# sokolov_control_board_3.net
KiCad netlist of a schematic drawn in Altium Designer
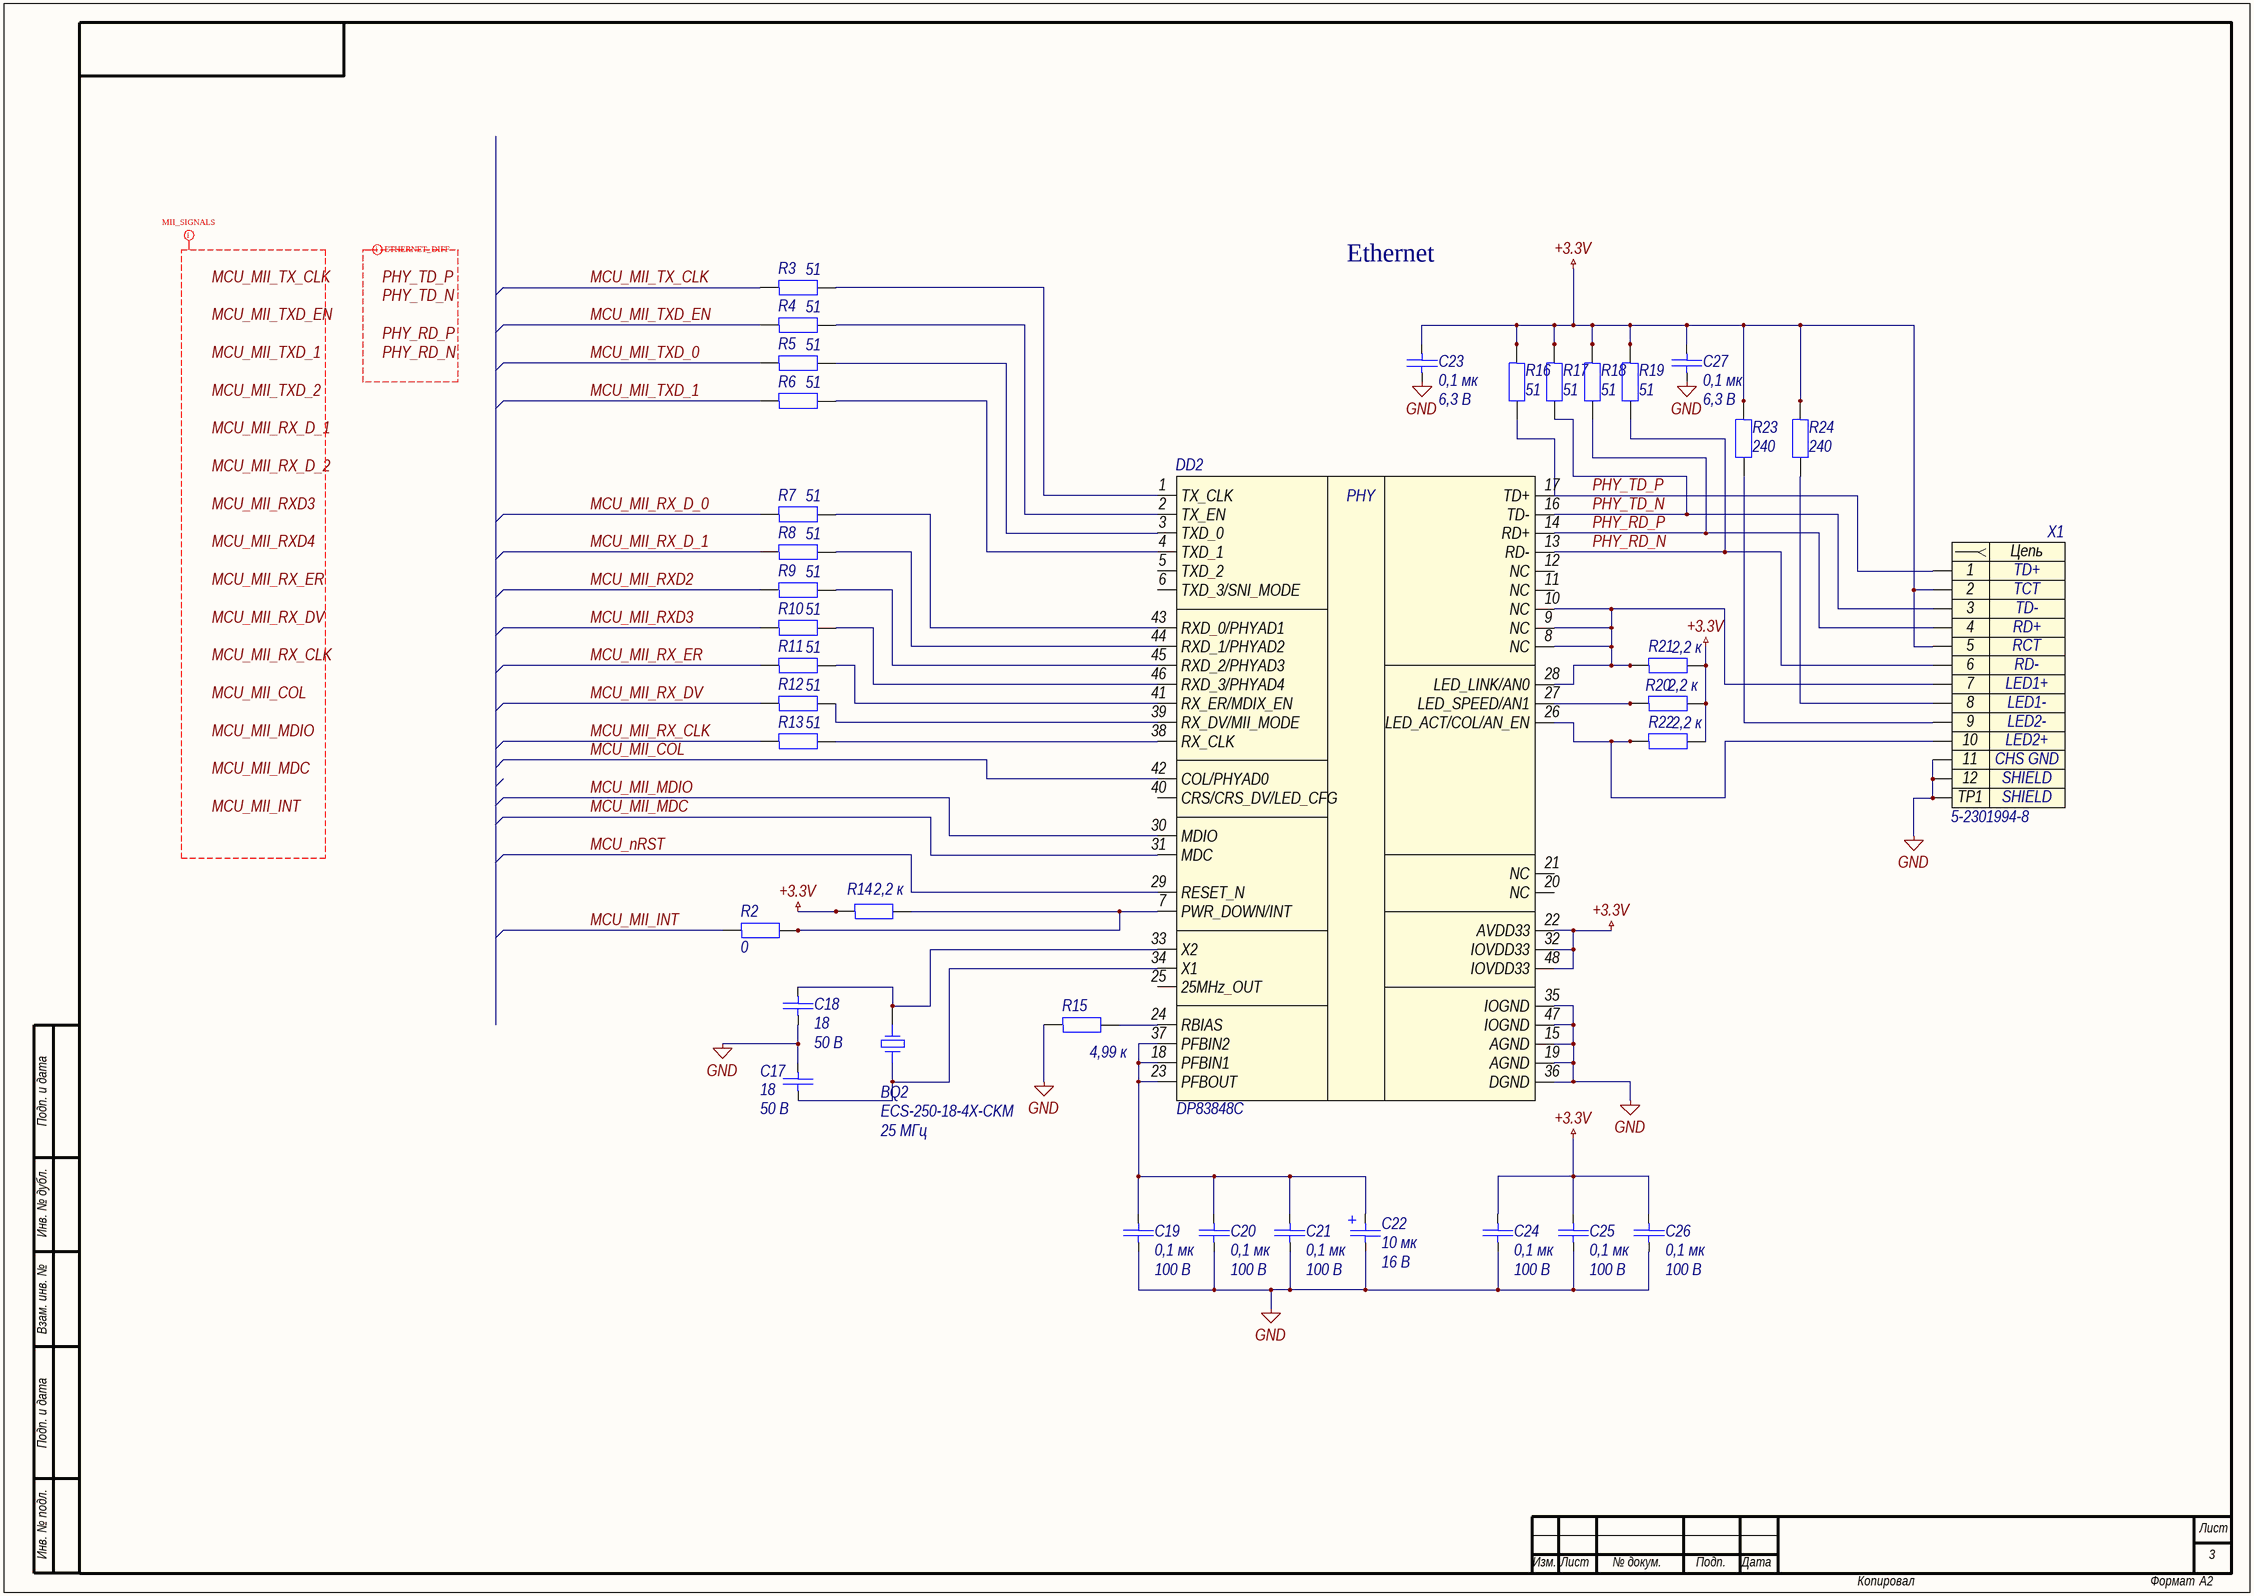
[diagram p0: sokolov_control_board_3.SchDoc]

(export (version "E")
  (design (tool "Eeschema 10.0.6"))
  (components
    (comp (ref "BQ2")
      (value "ECS-250-18-4X-CKM")
      (footprint "HC-49/US")
      (description "=Описание")
      (fields (field (name "ЧАСТОТA") "25 МГц"))
      (libsource (lib "Database_Students") (part "RESONATOR-COMMON"))
    )
    (comp (ref "C17")
      (value "18")
      (footprint "C0603")
      (description "=Описание")
      (fields (field (name "НАПРЯЖЕНИЕ") "50 В"))
      (libsource (lib "Database_Students") (part "CAPACITOR-NONPOLAR"))
    )
    (comp (ref "C18")
      (value "18")
      (footprint "C0603")
      (description "=Описание")
      (fields (field (name "НАПРЯЖЕНИЕ") "50 В"))
      (libsource (lib "Database_Students") (part "CAPACITOR-NONPOLAR"))
    )
    (comp (ref "C19")
      (value "0,1 мк")
      (footprint "C0603")
      (description "=Описание")
      (fields (field (name "НАПРЯЖЕНИЕ") "100 В"))
      (libsource (lib "Database_Students") (part "CAPACITOR-NONPOLAR"))
    )
    (comp (ref "C20")
      (value "0,1 мк")
      (footprint "C0603")
      (description "=Описание")
      (fields (field (name "НАПРЯЖЕНИЕ") "100 В"))
      (libsource (lib "Database_Students") (part "CAPACITOR-NONPOLAR"))
    )
    (comp (ref "C21")
      (value "0,1 мк")
      (footprint "C0603")
      (description "=Описание")
      (fields (field (name "НАПРЯЖЕНИЕ") "100 В"))
      (libsource (lib "Database_Students") (part "CAPACITOR-NONPOLAR"))
    )
    (comp (ref "C22")
      (value "10 мк")
      (footprint "C3216-18")
      (description "=Описание")
      (fields (field (name "НАПРЯЖЕНИЕ") "16 В"))
      (libsource (lib "Database_Students") (part "CAPACITOR-POLAR"))
    )
    (comp (ref "C23")
      (value "0,1 мк")
      (footprint "C0402")
      (description "=Описание")
      (fields (field (name "НАПРЯЖЕНИЕ") "6,3 В"))
      (libsource (lib "Database_Students") (part "CAPACITOR-NONPOLAR"))
    )
    (comp (ref "C24")
      (value "0,1 мк")
      (footprint "C0603")
      (description "=Описание")
      (fields (field (name "НАПРЯЖЕНИЕ") "100 В"))
      (libsource (lib "Database_Students") (part "CAPACITOR-NONPOLAR"))
    )
    (comp (ref "C25")
      (value "0,1 мк")
      (footprint "C0603")
      (description "=Описание")
      (fields (field (name "НАПРЯЖЕНИЕ") "100 В"))
      (libsource (lib "Database_Students") (part "CAPACITOR-NONPOLAR"))
    )
    (comp (ref "C26")
      (value "0,1 мк")
      (footprint "C0603")
      (description "=Описание")
      (fields (field (name "НАПРЯЖЕНИЕ") "100 В"))
      (libsource (lib "Database_Students") (part "CAPACITOR-NONPOLAR"))
    )
    (comp (ref "C27")
      (value "0,1 мк")
      (footprint "C0402")
      (description "=Описание")
      (fields (field (name "НАПРЯЖЕНИЕ") "6,3 В"))
      (libsource (lib "Database_Students") (part "CAPACITOR-NONPOLAR"))
    )
    (comp (ref "DD2")
      (value "DP83848C")
      (footprint "LQFP-48-P50-700X700X160-L60X22")
      (description "=Описание")
      (fields
        (field (name "PARTNUMBER") "DP83848CVV")
        (field (name "MANUFACTURER") "NationalSemiconductor")
        (field (name "COPYRIGHT") "Copyright (C) 2018 Accelerated Designs. All rights reserved")
        (field (name "PUBLISHER") "AltiumLimited")
      )
      (libsource (lib "Database_Students") (part "DP83848CVV"))
    )
    (comp (ref "R2")
      (value "0")
      (footprint "R0603")
      (description "=Описание")
      (libsource (lib "Database_Students") (part "RESISTOR-COMMON"))
    )
    (comp (ref "R3")
      (value "51")
      (footprint "R0603")
      (description "=Описание")
      (libsource (lib "Database_Students") (part "RESISTOR-COMMON"))
    )
    (comp (ref "R4")
      (value "51")
      (footprint "R0603")
      (description "=Описание")
      (libsource (lib "Database_Students") (part "RESISTOR-COMMON"))
    )
    (comp (ref "R5")
      (value "51")
      (footprint "R0603")
      (description "=Описание")
      (libsource (lib "Database_Students") (part "RESISTOR-COMMON"))
    )
    (comp (ref "R6")
      (value "51")
      (footprint "R0603")
      (description "=Описание")
      (libsource (lib "Database_Students") (part "RESISTOR-COMMON"))
    )
    (comp (ref "R7")
      (value "51")
      (footprint "R0603")
      (description "=Описание")
      (libsource (lib "Database_Students") (part "RESISTOR-COMMON"))
    )
    (comp (ref "R8")
      (value "51")
      (footprint "R0603")
      (description "=Описание")
      (libsource (lib "Database_Students") (part "RESISTOR-COMMON"))
    )
    (comp (ref "R9")
      (value "51")
      (footprint "R0603")
      (description "=Описание")
      (libsource (lib "Database_Students") (part "RESISTOR-COMMON"))
    )
    (comp (ref "R10")
      (value "51")
      (footprint "R0603")
      (description "=Описание")
      (libsource (lib "Database_Students") (part "RESISTOR-COMMON"))
    )
    (comp (ref "R11")
      (value "51")
      (footprint "R0603")
      (description "=Описание")
      (libsource (lib "Database_Students") (part "RESISTOR-COMMON"))
    )
    (comp (ref "R12")
      (value "51")
      (footprint "R0603")
      (description "=Описание")
      (libsource (lib "Database_Students") (part "RESISTOR-COMMON"))
    )
    (comp (ref "R13")
      (value "51")
      (footprint "R0603")
      (description "=Описание")
      (libsource (lib "Database_Students") (part "RESISTOR-COMMON"))
    )
    (comp (ref "R14")
      (value "2,2 к")
      (footprint "R0603")
      (description "=Описание")
      (libsource (lib "Database_Students") (part "RESISTOR-COMMON"))
    )
    (comp (ref "R15")
      (value "4,99 к")
      (footprint "R0603")
      (description "=Описание")
      (libsource (lib "Database_Students") (part "RESISTOR-COMMON"))
    )
    (comp (ref "R16")
      (value "51")
      (footprint "R0603")
      (description "=Описание")
      (libsource (lib "Database_Students") (part "RESISTOR-COMMON"))
    )
    (comp (ref "R17")
      (value "51")
      (footprint "R0603")
      (description "=Описание")
      (libsource (lib "Database_Students") (part "RESISTOR-COMMON"))
    )
    (comp (ref "R18")
      (value "51")
      (footprint "R0603")
      (description "=Описание")
      (libsource (lib "Database_Students") (part "RESISTOR-COMMON"))
    )
    (comp (ref "R19")
      (value "51")
      (footprint "R0603")
      (description "=Описание")
      (libsource (lib "Database_Students") (part "RESISTOR-COMMON"))
    )
    (comp (ref "R20")
      (value "2,2 к")
      (footprint "R0603")
      (description "=Описание")
      (libsource (lib "Database_Students") (part "RESISTOR-COMMON"))
    )
    (comp (ref "R21")
      (value "2,2 к")
      (footprint "R0603")
      (description "=Описание")
      (libsource (lib "Database_Students") (part "RESISTOR-COMMON"))
    )
    (comp (ref "R22")
      (value "2,2 к")
      (footprint "R0603")
      (description "=Описание")
      (libsource (lib "Database_Students") (part "RESISTOR-COMMON"))
    )
    (comp (ref "R23")
      (value "240")
      (footprint "R0603")
      (description "=Описание")
      (libsource (lib "Database_Students") (part "RESISTOR-COMMON"))
    )
    (comp (ref "R24")
      (value "240")
      (footprint "R0603")
      (description "=Описание")
      (libsource (lib "Database_Students") (part "RESISTOR-COMMON"))
    )
    (comp (ref "X1")
      (value "5-2301994-8")
      (footprint "5-2301994-8")
      (description "=Описание")
      (libsource (lib "Database_Students") (part "HEADER-12-TP1-SCT"))
    )
  )
  (nets
    (net (code "1") (name "+3.3V") (class "Default")
      (node (ref "C23") (pin "2") (pinfunction "2_2") (pintype "passive"))
      (node (ref "C24") (pin "2") (pinfunction "2_2") (pintype "passive"))
      (node (ref "C25") (pin "2") (pinfunction "2_2") (pintype "passive"))
      (node (ref "C26") (pin "2") (pinfunction "2_2") (pintype "passive"))
      (node (ref "C27") (pin "2") (pinfunction "2_2") (pintype "passive"))
      (node (ref "DD2") (pin "22") (pinfunction "AVDD33_22") (pintype "power_in"))
      (node (ref "DD2") (pin "32") (pinfunction "IOVDD33_32") (pintype "power_in"))
      (node (ref "DD2") (pin "48") (pinfunction "IOVDD33_48") (pintype "power_in"))
      (node (ref "R14") (pin "1") (pinfunction "1_1") (pintype "passive"))
      (node (ref "R16") (pin "1") (pinfunction "1_1") (pintype "passive"))
      (node (ref "R17") (pin "1") (pinfunction "1_1") (pintype "passive"))
      (node (ref "R18") (pin "1") (pinfunction "1_1") (pintype "passive"))
      (node (ref "R19") (pin "1") (pinfunction "1_1") (pintype "passive"))
      (node (ref "R20") (pin "2") (pinfunction "2_2") (pintype "passive"))
      (node (ref "R21") (pin "2") (pinfunction "2_2") (pintype "passive"))
      (node (ref "R22") (pin "2") (pinfunction "2_2") (pintype "passive"))
      (node (ref "R23") (pin "1") (pinfunction "1_1") (pintype "passive"))
      (node (ref "R24") (pin "1") (pinfunction "1_1") (pintype "passive"))
      (node (ref "X1") (pin "2") (pinfunction "2_2") (pintype "passive"))
      (node (ref "X1") (pin "5") (pinfunction "5_5") (pintype "passive"))
    )
    (net (code "2") (name "/MCU_MII_COL") (class "Default")
      (node (ref "DD2") (pin "42") (pinfunction "COL/PHYAD0_42") (pintype "power_in"))
    )
    (net (code "3") (name "/MCU_MII_INT") (class "Default")
      (node (ref "R2") (pin "1") (pinfunction "1_1") (pintype "passive"))
    )
    (net (code "4") (name "/MCU_MII_MDC") (class "Default")
      (node (ref "DD2") (pin "31") (pinfunction "MDC_31") (pintype "power_in"))
    )
    (net (code "5") (name "/MCU_MII_MDIO") (class "Default")
      (node (ref "DD2") (pin "30") (pinfunction "MDIO_30") (pintype "power_in"))
    )
    (net (code "6") (name "/MCU_MII_RXD2") (class "Default")
      (node (ref "R9") (pin "1") (pinfunction "1_1") (pintype "passive"))
    )
    (net (code "7") (name "/MCU_MII_RXD3") (class "Default")
      (node (ref "R10") (pin "1") (pinfunction "1_1") (pintype "passive"))
    )
    (net (code "9") (name "/MCU_MII_RX_CLK") (class "Default")
      (node (ref "R13") (pin "1") (pinfunction "1_1") (pintype "passive"))
    )
    (net (code "10") (name "/MCU_MII_RX_DV") (class "Default")
      (node (ref "R12") (pin "1") (pinfunction "1_1") (pintype "passive"))
    )
    (net (code "11") (name "/MCU_MII_RX_D_0") (class "Default")
      (node (ref "R7") (pin "1") (pinfunction "1_1") (pintype "passive"))
    )
    (net (code "12") (name "/MCU_MII_RX_D_1") (class "Default")
      (node (ref "R8") (pin "1") (pinfunction "1_1") (pintype "passive"))
    )
    (net (code "14") (name "/MCU_MII_RX_ER") (class "Default")
      (node (ref "R11") (pin "1") (pinfunction "1_1") (pintype "passive"))
    )
    (net (code "15") (name "/MCU_MII_TXD_0") (class "Default")
      (node (ref "R5") (pin "1") (pinfunction "1_1") (pintype "passive"))
    )
    (net (code "16") (name "/MCU_MII_TXD_1") (class "Default")
      (node (ref "R6") (pin "1") (pinfunction "1_1") (pintype "passive"))
    )
    (net (code "18") (name "/MCU_MII_TXD_EN") (class "Default")
      (node (ref "R4") (pin "1") (pinfunction "1_1") (pintype "passive"))
    )
    (net (code "19") (name "/MCU_MII_TX_CLK") (class "Default")
      (node (ref "R3") (pin "1") (pinfunction "1_1") (pintype "passive"))
    )
    (net (code "20") (name "/MCU_nRST") (class "Default")
      (node (ref "DD2") (pin "29") (pinfunction "RESET_N_29") (pintype "power_in"))
    )
    (net (code "21") (name "/PHY_RD_N") (class "Default")
      (node (ref "DD2") (pin "13") (pinfunction "RD-_13") (pintype "power_in"))
      (node (ref "R19") (pin "2") (pinfunction "2_2") (pintype "passive"))
      (node (ref "X1") (pin "6") (pinfunction "6_6") (pintype "passive"))
    )
    (net (code "22") (name "/PHY_RD_P") (class "Default")
      (node (ref "DD2") (pin "14") (pinfunction "RD+_14") (pintype "power_in"))
      (node (ref "R18") (pin "2") (pinfunction "2_2") (pintype "passive"))
      (node (ref "X1") (pin "4") (pinfunction "4_4") (pintype "passive"))
    )
    (net (code "23") (name "/PHY_TD_N") (class "Default")
      (node (ref "DD2") (pin "16") (pinfunction "TD-_16") (pintype "power_in"))
      (node (ref "R17") (pin "2") (pinfunction "2_2") (pintype "passive"))
      (node (ref "X1") (pin "3") (pinfunction "3_3") (pintype "passive"))
    )
    (net (code "24") (name "/PHY_TD_P") (class "Default")
      (node (ref "DD2") (pin "17") (pinfunction "TD+_17") (pintype "power_in"))
      (node (ref "R16") (pin "2") (pinfunction "2_2") (pintype "passive"))
      (node (ref "X1") (pin "1") (pinfunction "1_1") (pintype "passive"))
    )
    (net (code "25") (name "GND") (class "Default")
      (node (ref "C17") (pin "2") (pinfunction "2_2") (pintype "passive"))
      (node (ref "C18") (pin "1") (pinfunction "1_1") (pintype "passive"))
      (node (ref "C19") (pin "1") (pinfunction "1_1") (pintype "passive"))
      (node (ref "C20") (pin "1") (pinfunction "1_1") (pintype "passive"))
      (node (ref "C21") (pin "1") (pinfunction "1_1") (pintype "passive"))
      (node (ref "C22") (pin "2") (pinfunction "2_2") (pintype "passive"))
      (node (ref "C23") (pin "1") (pinfunction "1_1") (pintype "passive"))
      (node (ref "C24") (pin "1") (pinfunction "1_1") (pintype "passive"))
      (node (ref "C25") (pin "1") (pinfunction "1_1") (pintype "passive"))
      (node (ref "C26") (pin "1") (pinfunction "1_1") (pintype "passive"))
      (node (ref "C27") (pin "1") (pinfunction "1_1") (pintype "passive"))
      (node (ref "DD2") (pin "15") (pinfunction "AGND_15") (pintype "power_in"))
      (node (ref "DD2") (pin "19") (pinfunction "AGND_19") (pintype "power_in"))
      (node (ref "DD2") (pin "35") (pinfunction "IOGND_35") (pintype "power_in"))
      (node (ref "DD2") (pin "36") (pinfunction "DGND_36") (pintype "power_in"))
      (node (ref "DD2") (pin "47") (pinfunction "IOGND_47") (pintype "power_in"))
      (node (ref "R15") (pin "1") (pinfunction "1_1") (pintype "passive"))
      (node (ref "X1") (pin "11") (pinfunction "11_11") (pintype "passive"))
      (node (ref "X1") (pin "12") (pinfunction "12_12") (pintype "passive"))
      (node (ref "X1") (pin "TP1") (pinfunction "TP1_TP1") (pintype "passive"))
    )
    (net (code "26") (name "Net-(DD2-LED_ACT{slash}COL{slash}AN_EN)") (class "Default")
      (node (ref "DD2") (pin "26") (pinfunction "LED_ACT/COL/AN_EN_26") (pintype "power_in"))
      (node (ref "R22") (pin "1") (pinfunction "1_1") (pintype "passive"))
      (node (ref "X1") (pin "10") (pinfunction "10_10") (pintype "passive"))
    )
    (net (code "27") (name "Net-(DD2-LED_LINK{slash}AN0)") (class "Default")
      (node (ref "DD2") (pin "10") (pinfunction "NC_10") (pintype "power_in"))
      (node (ref "DD2") (pin "28") (pinfunction "LED_LINK/AN0_28") (pintype "power_in"))
      (node (ref "DD2") (pin "8") (pinfunction "NC_8") (pintype "power_in"))
      (node (ref "DD2") (pin "9") (pinfunction "NC_9") (pintype "power_in"))
      (node (ref "R21") (pin "1") (pinfunction "1_1") (pintype "passive"))
      (node (ref "X1") (pin "7") (pinfunction "7_7") (pintype "passive"))
    )
    (net (code "28") (name "Net-(DD2-LED_SPEED{slash}AN1)") (class "Default")
      (node (ref "DD2") (pin "27") (pinfunction "LED_SPEED/AN1_27") (pintype "power_in"))
      (node (ref "R20") (pin "1") (pinfunction "1_1") (pintype "passive"))
    )
    (net (code "29") (name "Net-(DD2-PFBIN1)") (class "Default")
      (node (ref "C19") (pin "2") (pinfunction "2_2") (pintype "passive"))
      (node (ref "C20") (pin "2") (pinfunction "2_2") (pintype "passive"))
      (node (ref "C21") (pin "2") (pinfunction "2_2") (pintype "passive"))
      (node (ref "C22") (pin "1") (pinfunction "1_1") (pintype "passive"))
      (node (ref "DD2") (pin "18") (pinfunction "PFBIN1_18") (pintype "power_in"))
      (node (ref "DD2") (pin "23") (pinfunction "PFBOUT_23") (pintype "power_in"))
      (node (ref "DD2") (pin "37") (pinfunction "PFBIN2_37") (pintype "power_in"))
    )
    (net (code "30") (name "Net-(DD2-PWR_DOWN{slash}INT)") (class "Default")
      (node (ref "DD2") (pin "7") (pinfunction "PWR_DOWN/INT_7") (pintype "power_in"))
      (node (ref "R14") (pin "2") (pinfunction "2_2") (pintype "passive"))
      (node (ref "R2") (pin "2") (pinfunction "2_2") (pintype "passive"))
    )
    (net (code "31") (name "Net-(DD2-RBIAS)") (class "Default")
      (node (ref "DD2") (pin "24") (pinfunction "RBIAS_24") (pintype "power_in"))
      (node (ref "R15") (pin "2") (pinfunction "2_2") (pintype "passive"))
    )
    (net (code "32") (name "Net-(DD2-RXD_0{slash}PHYAD1)") (class "Default")
      (node (ref "DD2") (pin "43") (pinfunction "RXD_0/PHYAD1_43") (pintype "power_in"))
      (node (ref "R7") (pin "2") (pinfunction "2_2") (pintype "passive"))
    )
    (net (code "33") (name "Net-(DD2-RXD_1{slash}PHYAD2)") (class "Default")
      (node (ref "DD2") (pin "44") (pinfunction "RXD_1/PHYAD2_44") (pintype "power_in"))
      (node (ref "R8") (pin "2") (pinfunction "2_2") (pintype "passive"))
    )
    (net (code "34") (name "Net-(DD2-RXD_2{slash}PHYAD3)") (class "Default")
      (node (ref "DD2") (pin "45") (pinfunction "RXD_2/PHYAD3_45") (pintype "power_in"))
      (node (ref "R9") (pin "2") (pinfunction "2_2") (pintype "passive"))
    )
    (net (code "35") (name "Net-(DD2-RXD_3{slash}PHYAD4)") (class "Default")
      (node (ref "DD2") (pin "46") (pinfunction "RXD_3/PHYAD4_46") (pintype "power_in"))
      (node (ref "R10") (pin "2") (pinfunction "2_2") (pintype "passive"))
    )
    (net (code "36") (name "Net-(DD2-RX_CLK)") (class "Default")
      (node (ref "DD2") (pin "38") (pinfunction "RX_CLK_38") (pintype "power_in"))
      (node (ref "R13") (pin "2") (pinfunction "2_2") (pintype "passive"))
    )
    (net (code "37") (name "Net-(DD2-RX_DV{slash}MII_MODE)") (class "Default")
      (node (ref "DD2") (pin "39") (pinfunction "RX_DV/MII_MODE_39") (pintype "power_in"))
      (node (ref "R12") (pin "2") (pinfunction "2_2") (pintype "passive"))
    )
    (net (code "38") (name "Net-(DD2-RX_ER{slash}MDIX_EN)") (class "Default")
      (node (ref "DD2") (pin "41") (pinfunction "RX_ER/MDIX_EN_41") (pintype "power_in"))
      (node (ref "R11") (pin "2") (pinfunction "2_2") (pintype "passive"))
    )
    (net (code "39") (name "Net-(DD2-TXD_0)") (class "Default")
      (node (ref "DD2") (pin "3") (pinfunction "TXD_0_3") (pintype "power_in"))
      (node (ref "R5") (pin "2") (pinfunction "2_2") (pintype "passive"))
    )
    (net (code "40") (name "Net-(DD2-TXD_1)") (class "Default")
      (node (ref "DD2") (pin "4") (pinfunction "TXD_1_4") (pintype "power_in"))
      (node (ref "R6") (pin "2") (pinfunction "2_2") (pintype "passive"))
    )
    (net (code "41") (name "Net-(DD2-TX_CLK)") (class "Default")
      (node (ref "DD2") (pin "1") (pinfunction "TX_CLK_1") (pintype "power_in"))
      (node (ref "R3") (pin "2") (pinfunction "2_2") (pintype "passive"))
    )
    (net (code "42") (name "Net-(DD2-TX_EN)") (class "Default")
      (node (ref "DD2") (pin "2") (pinfunction "TX_EN_2") (pintype "power_in"))
      (node (ref "R4") (pin "2") (pinfunction "2_2") (pintype "passive"))
    )
    (net (code "43") (name "Net-(DD2-X1)") (class "Default")
      (node (ref "BQ2") (pin "1") (pinfunction "1_1") (pintype "passive"))
      (node (ref "C17") (pin "1") (pinfunction "1_1") (pintype "passive"))
      (node (ref "DD2") (pin "34") (pinfunction "X1_34") (pintype "power_in"))
    )
    (net (code "44") (name "Net-(DD2-X2)") (class "Default")
      (node (ref "BQ2") (pin "2") (pinfunction "2_2") (pintype "passive"))
      (node (ref "C18") (pin "2") (pinfunction "2_2") (pintype "passive"))
      (node (ref "DD2") (pin "33") (pinfunction "X2_33") (pintype "power_in"))
    )
    (net (code "45") (name "Net-(R23-Pad2)") (class "Default")
      (node (ref "R23") (pin "2") (pinfunction "2_2") (pintype "passive"))
      (node (ref "X1") (pin "9") (pinfunction "9_9") (pintype "passive"))
    )
    (net (code "46") (name "Net-(R24-Pad2)") (class "Default")
      (node (ref "R24") (pin "2") (pinfunction "2_2") (pintype "passive"))
      (node (ref "X1") (pin "8") (pinfunction "8_8") (pintype "passive"))
    )
    (net (code "47") (name "unconnected-(DD2-25MHz_OUT-Pad25)") (class "Default")
      (node (ref "DD2") (pin "25") (pinfunction "25MHz_OUT_25") (pintype "power_in"))
    )
    (net (code "48") (name "unconnected-(DD2-CRS{slash}CRS_DV{slash}LED_CFG-Pad40)") (class "Default")
      (node (ref "DD2") (pin "40") (pinfunction "CRS/CRS_DV/LED_CFG_40") (pintype "power_in"))
    )
    (net (code "49") (name "unconnected-(DD2-NC-Pad11)") (class "Default")
      (node (ref "DD2") (pin "11") (pinfunction "NC_11") (pintype "power_in"))
    )
    (net (code "50") (name "unconnected-(DD2-NC-Pad12)") (class "Default")
      (node (ref "DD2") (pin "12") (pinfunction "NC_12") (pintype "power_in"))
    )
    (net (code "51") (name "unconnected-(DD2-NC-Pad20)") (class "Default")
      (node (ref "DD2") (pin "20") (pinfunction "NC_20") (pintype "power_in"))
    )
    (net (code "52") (name "unconnected-(DD2-NC-Pad21)") (class "Default")
      (node (ref "DD2") (pin "21") (pinfunction "NC_21") (pintype "power_in"))
    )
    (net (code "53") (name "unconnected-(DD2-TXD_2-Pad5)") (class "Default")
      (node (ref "DD2") (pin "5") (pinfunction "TXD_2_5") (pintype "power_in"))
    )
    (net (code "54") (name "unconnected-(DD2-TXD_3{slash}SNI_MODE-Pad6)") (class "Default")
      (node (ref "DD2") (pin "6") (pinfunction "TXD_3/SNI_MODE_6") (pintype "power_in"))
    )
  )
)
